# poorUSBadapter.net
KiCad netlist of a schematic drawn in EAGLE
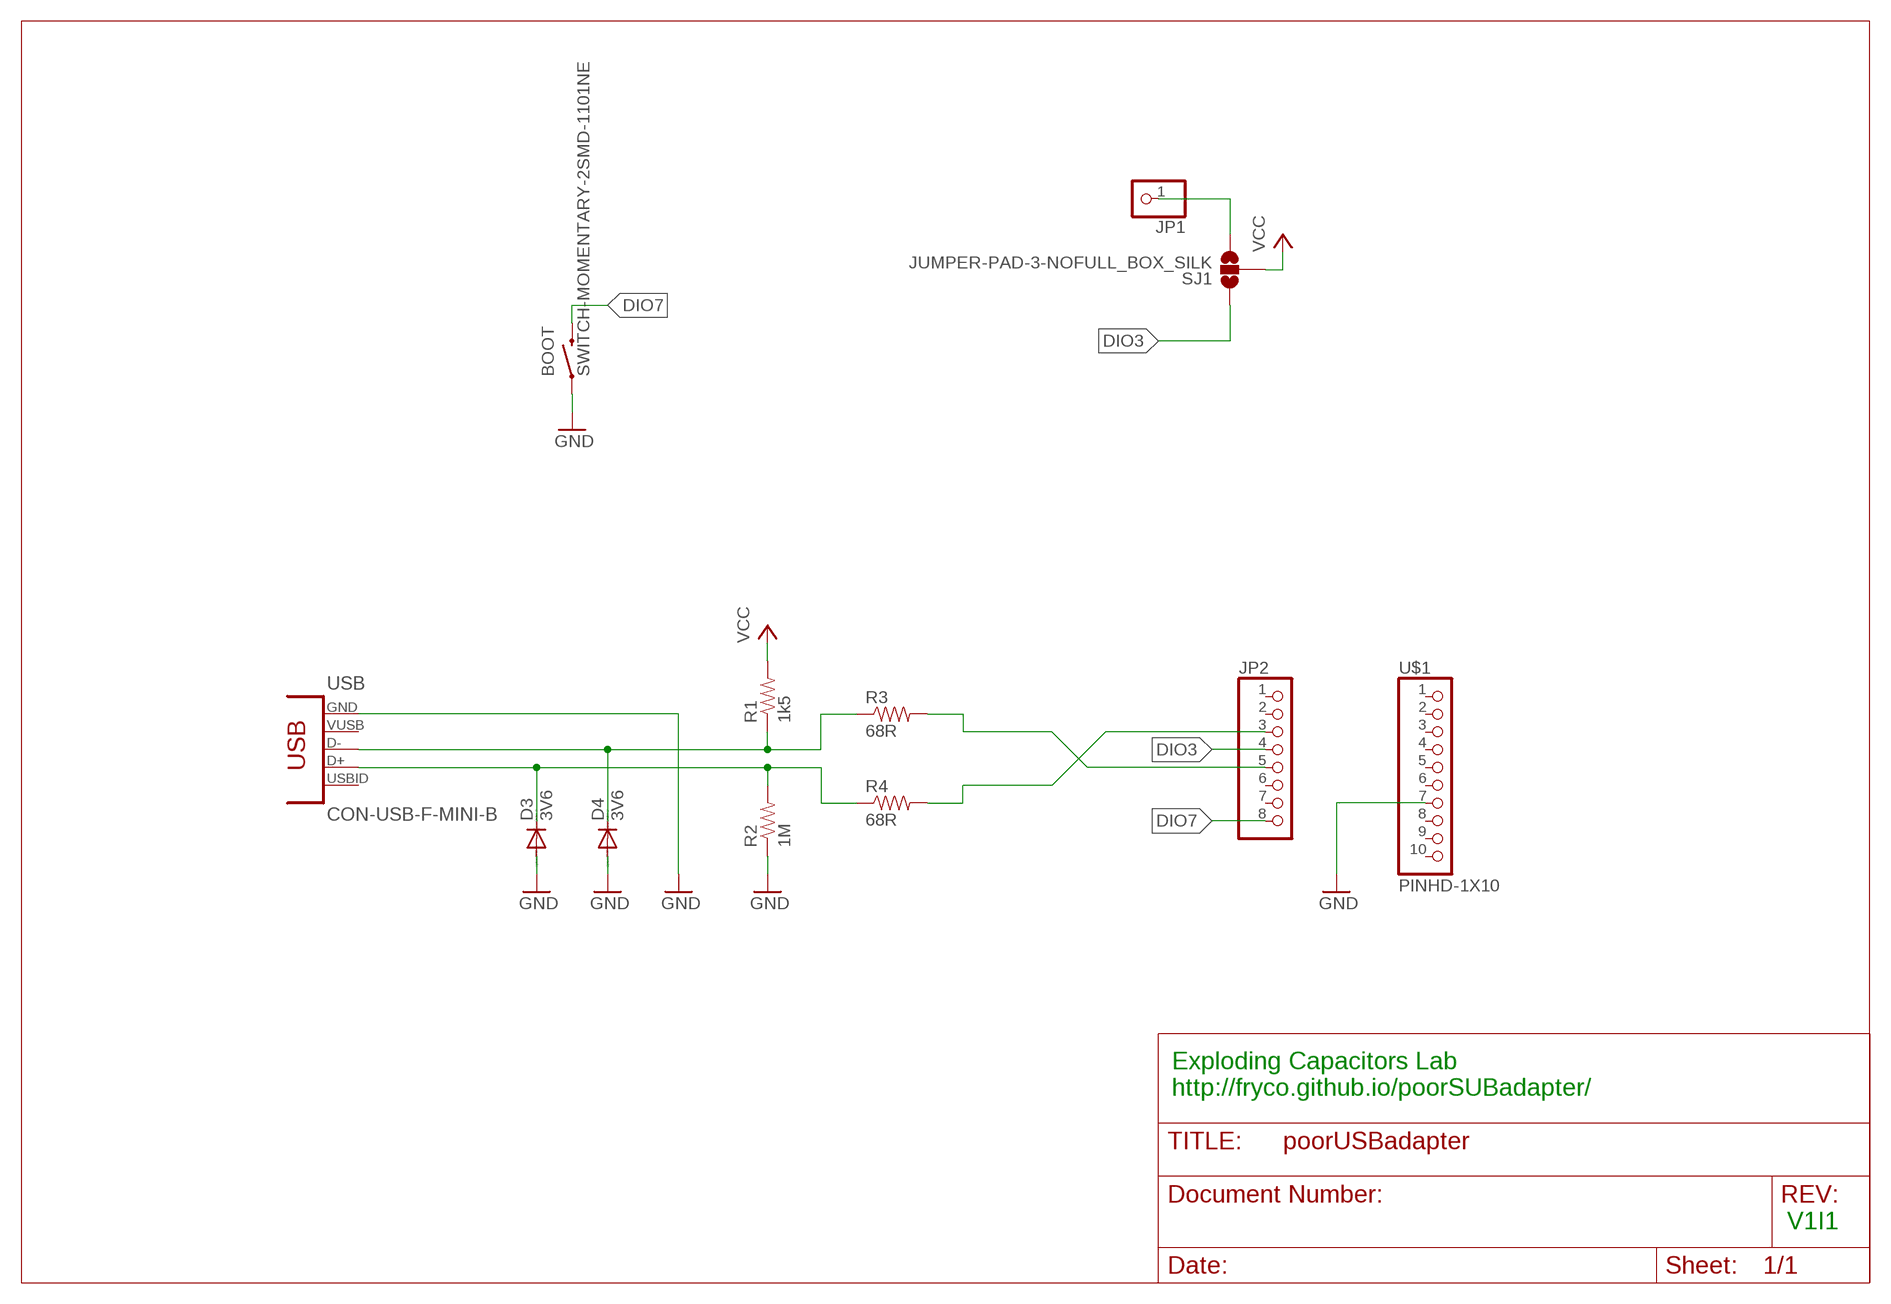
[diagram p0: schematic, sheet 1]

(export (version "E")
  (design (tool "Eeschema 10.0.6"))
  (components
    (comp (ref "BOOT")
      (value "SWITCH-MOMENTARY-2SMD-1101NE")
      (footprint "eagle-import:TACTILE-SWITCH-1101NE")
      (libsource (lib "eagle-import") (part "SWITCH-MOMENTARY-2SMD-1101NE"))
    )
    (comp (ref "D3")
      (value "3V6")
      (footprint "eagle-import:MICROMELF-W")
      (libsource (lib "eagle-import") (part "DIODE-MICROMELF-W"))
    )
    (comp (ref "D4")
      (value "3V6")
      (footprint "eagle-import:MICROMELF-W")
      (libsource (lib "eagle-import") (part "DIODE-MICROMELF-W"))
    )
    (comp (ref "JP1")
      (value "PINHD-1X1")
      (footprint "eagle-import:1X01")
      (libsource (lib "eagle-import") (part "PINHD-1X1"))
    )
    (comp (ref "JP2")
      (value "PINHD-1X8BIG")
      (footprint "eagle-import:1X08-BIG")
      (libsource (lib "eagle-import") (part "PINHD-1X8BIG"))
    )
    (comp (ref "R1")
      (value "1k5")
      (footprint "eagle-import:0805")
      (libsource (lib "eagle-import") (part "RESISTOR0805-RES"))
    )
    (comp (ref "R2")
      (value "1M")
      (footprint "eagle-import:0805")
      (libsource (lib "eagle-import") (part "RESISTOR0805-RES"))
    )
    (comp (ref "R3")
      (value "68R")
      (footprint "eagle-import:0805")
      (libsource (lib "eagle-import") (part "RESISTOR0805-RES"))
    )
    (comp (ref "R4")
      (value "68R")
      (footprint "eagle-import:0805")
      (libsource (lib "eagle-import") (part "RESISTOR0805-RES"))
    )
    (comp (ref "SJ1")
      (value "JUMPER-PAD-3-NOFULL_BOX_SILK")
      (footprint "eagle-import:PAD-JUMPER-3-NO_YES_SILK_FULL_BOX")
      (libsource (lib "eagle-import") (part "JUMPER-PAD-3-NOFULL_BOX_SILK"))
    )
    (comp (ref "U$1")
      (value "PINHD-1X10")
      (footprint "eagle-import:1X10-BIG")
      (libsource (lib "eagle-import") (part "PINHD-1X10"))
    )
    (comp (ref "USB")
      (value "CON-USB-F-MINI-B")
      (footprint "eagle-import:CONN_USB_MINI-B")
      (libsource (lib "eagle-import") (part "CON-USB-F-MINI-B"))
    )
  )
  (nets
    (net (code "1") (name "DIO3") (class "Default")
      (node (ref "JP2") (pin "4") (pinfunction "4_4") (pintype "passive"))
      (node (ref "SJ1") (pin "1") (pinfunction "1_1") (pintype "passive"))
    )
    (net (code "2") (name "DIO7") (class "Default")
      (node (ref "BOOT") (pin "2") (pinfunction "2_2") (pintype "passive"))
      (node (ref "JP2") (pin "8") (pinfunction "8_8") (pintype "passive"))
    )
    (net (code "3") (name "GND") (class "Default")
      (node (ref "BOOT") (pin "1") (pinfunction "1_1") (pintype "passive"))
      (node (ref "D3") (pin "A") (pinfunction "A_A") (pintype "passive"))
      (node (ref "D4") (pin "A") (pinfunction "A_A") (pintype "passive"))
      (node (ref "R2") (pin "1") (pinfunction "1_1") (pintype "passive"))
      (node (ref "U$1") (pin "7") (pinfunction "7_7") (pintype "passive"))
      (node (ref "USB") (pin "GND") (pinfunction "GND_GND") (pintype "bidirectional"))
    )
    (net (code "4") (name "Net-(D3-PadC)") (class "Default")
      (node (ref "D3") (pin "C") (pinfunction "C_C") (pintype "passive"))
      (node (ref "R2") (pin "2") (pinfunction "2_2") (pintype "passive"))
      (node (ref "R4") (pin "1") (pinfunction "1_1") (pintype "passive"))
      (node (ref "USB") (pin "D+") (pinfunction "D+_D+") (pintype "bidirectional"))
    )
    (net (code "5") (name "Net-(D4-PadC)") (class "Default")
      (node (ref "D4") (pin "C") (pinfunction "C_C") (pintype "passive"))
      (node (ref "R1") (pin "1") (pinfunction "1_1") (pintype "passive"))
      (node (ref "R3") (pin "1") (pinfunction "1_1") (pintype "passive"))
      (node (ref "USB") (pin "D-") (pinfunction "D-_D-") (pintype "bidirectional"))
    )
    (net (code "6") (name "Net-(JP1-Pad1)") (class "Default")
      (node (ref "JP1") (pin "1") (pinfunction "1_1") (pintype "passive"))
      (node (ref "SJ1") (pin "3") (pinfunction "3_3") (pintype "passive"))
    )
    (net (code "7") (name "Net-(JP2-Pad3)") (class "Default")
      (node (ref "JP2") (pin "3") (pinfunction "3_3") (pintype "passive"))
      (node (ref "R4") (pin "2") (pinfunction "2_2") (pintype "passive"))
    )
    (net (code "8") (name "Net-(JP2-Pad5)") (class "Default")
      (node (ref "JP2") (pin "5") (pinfunction "5_5") (pintype "passive"))
      (node (ref "R3") (pin "2") (pinfunction "2_2") (pintype "passive"))
    )
    (net (code "9") (name "VCC") (class "Default")
      (node (ref "R1") (pin "2") (pinfunction "2_2") (pintype "passive"))
      (node (ref "SJ1") (pin "2") (pinfunction "2_2") (pintype "passive"))
    )
    (net (code "10") (name "unconnected-(JP2-Pad1)") (class "Default")
      (node (ref "JP2") (pin "1") (pinfunction "1_1") (pintype "passive"))
    )
    (net (code "11") (name "unconnected-(JP2-Pad2)") (class "Default")
      (node (ref "JP2") (pin "2") (pinfunction "2_2") (pintype "passive"))
    )
    (net (code "12") (name "unconnected-(JP2-Pad6)") (class "Default")
      (node (ref "JP2") (pin "6") (pinfunction "6_6") (pintype "passive"))
    )
    (net (code "13") (name "unconnected-(JP2-Pad7)") (class "Default")
      (node (ref "JP2") (pin "7") (pinfunction "7_7") (pintype "passive"))
    )
    (net (code "14") (name "unconnected-(U$1-Pad1)") (class "Default")
      (node (ref "U$1") (pin "1") (pinfunction "1_1") (pintype "passive"))
    )
    (net (code "15") (name "unconnected-(U$1-Pad2)") (class "Default")
      (node (ref "U$1") (pin "2") (pinfunction "2_2") (pintype "passive"))
    )
    (net (code "16") (name "unconnected-(U$1-Pad3)") (class "Default")
      (node (ref "U$1") (pin "3") (pinfunction "3_3") (pintype "passive"))
    )
    (net (code "17") (name "unconnected-(U$1-Pad4)") (class "Default")
      (node (ref "U$1") (pin "4") (pinfunction "4_4") (pintype "passive"))
    )
    (net (code "18") (name "unconnected-(U$1-Pad5)") (class "Default")
      (node (ref "U$1") (pin "5") (pinfunction "5_5") (pintype "passive"))
    )
    (net (code "19") (name "unconnected-(U$1-Pad6)") (class "Default")
      (node (ref "U$1") (pin "6") (pinfunction "6_6") (pintype "passive"))
    )
    (net (code "20") (name "unconnected-(U$1-Pad8)") (class "Default")
      (node (ref "U$1") (pin "8") (pinfunction "8_8") (pintype "passive"))
    )
    (net (code "21") (name "unconnected-(U$1-Pad9)") (class "Default")
      (node (ref "U$1") (pin "9") (pinfunction "9_9") (pintype "passive"))
    )
    (net (code "22") (name "unconnected-(U$1-Pad10)") (class "Default")
      (node (ref "U$1") (pin "10") (pinfunction "10_10") (pintype "passive"))
    )
    (net (code "23") (name "unconnected-(USB-PadVUSB)") (class "Default")
      (node (ref "USB") (pin "VUSB") (pinfunction "VUSB_VUSB") (pintype "bidirectional"))
    )
    (net (code "24") (name "unconnected-(USBB-USBID-PadID)") (class "Default")
      (node (ref "USB") (pin "ID") (pinfunction "USBID_ID") (pintype "bidirectional"))
    )
  )
)
